# 04_io.net
KiCad netlist of a schematic drawn in Altium Designer
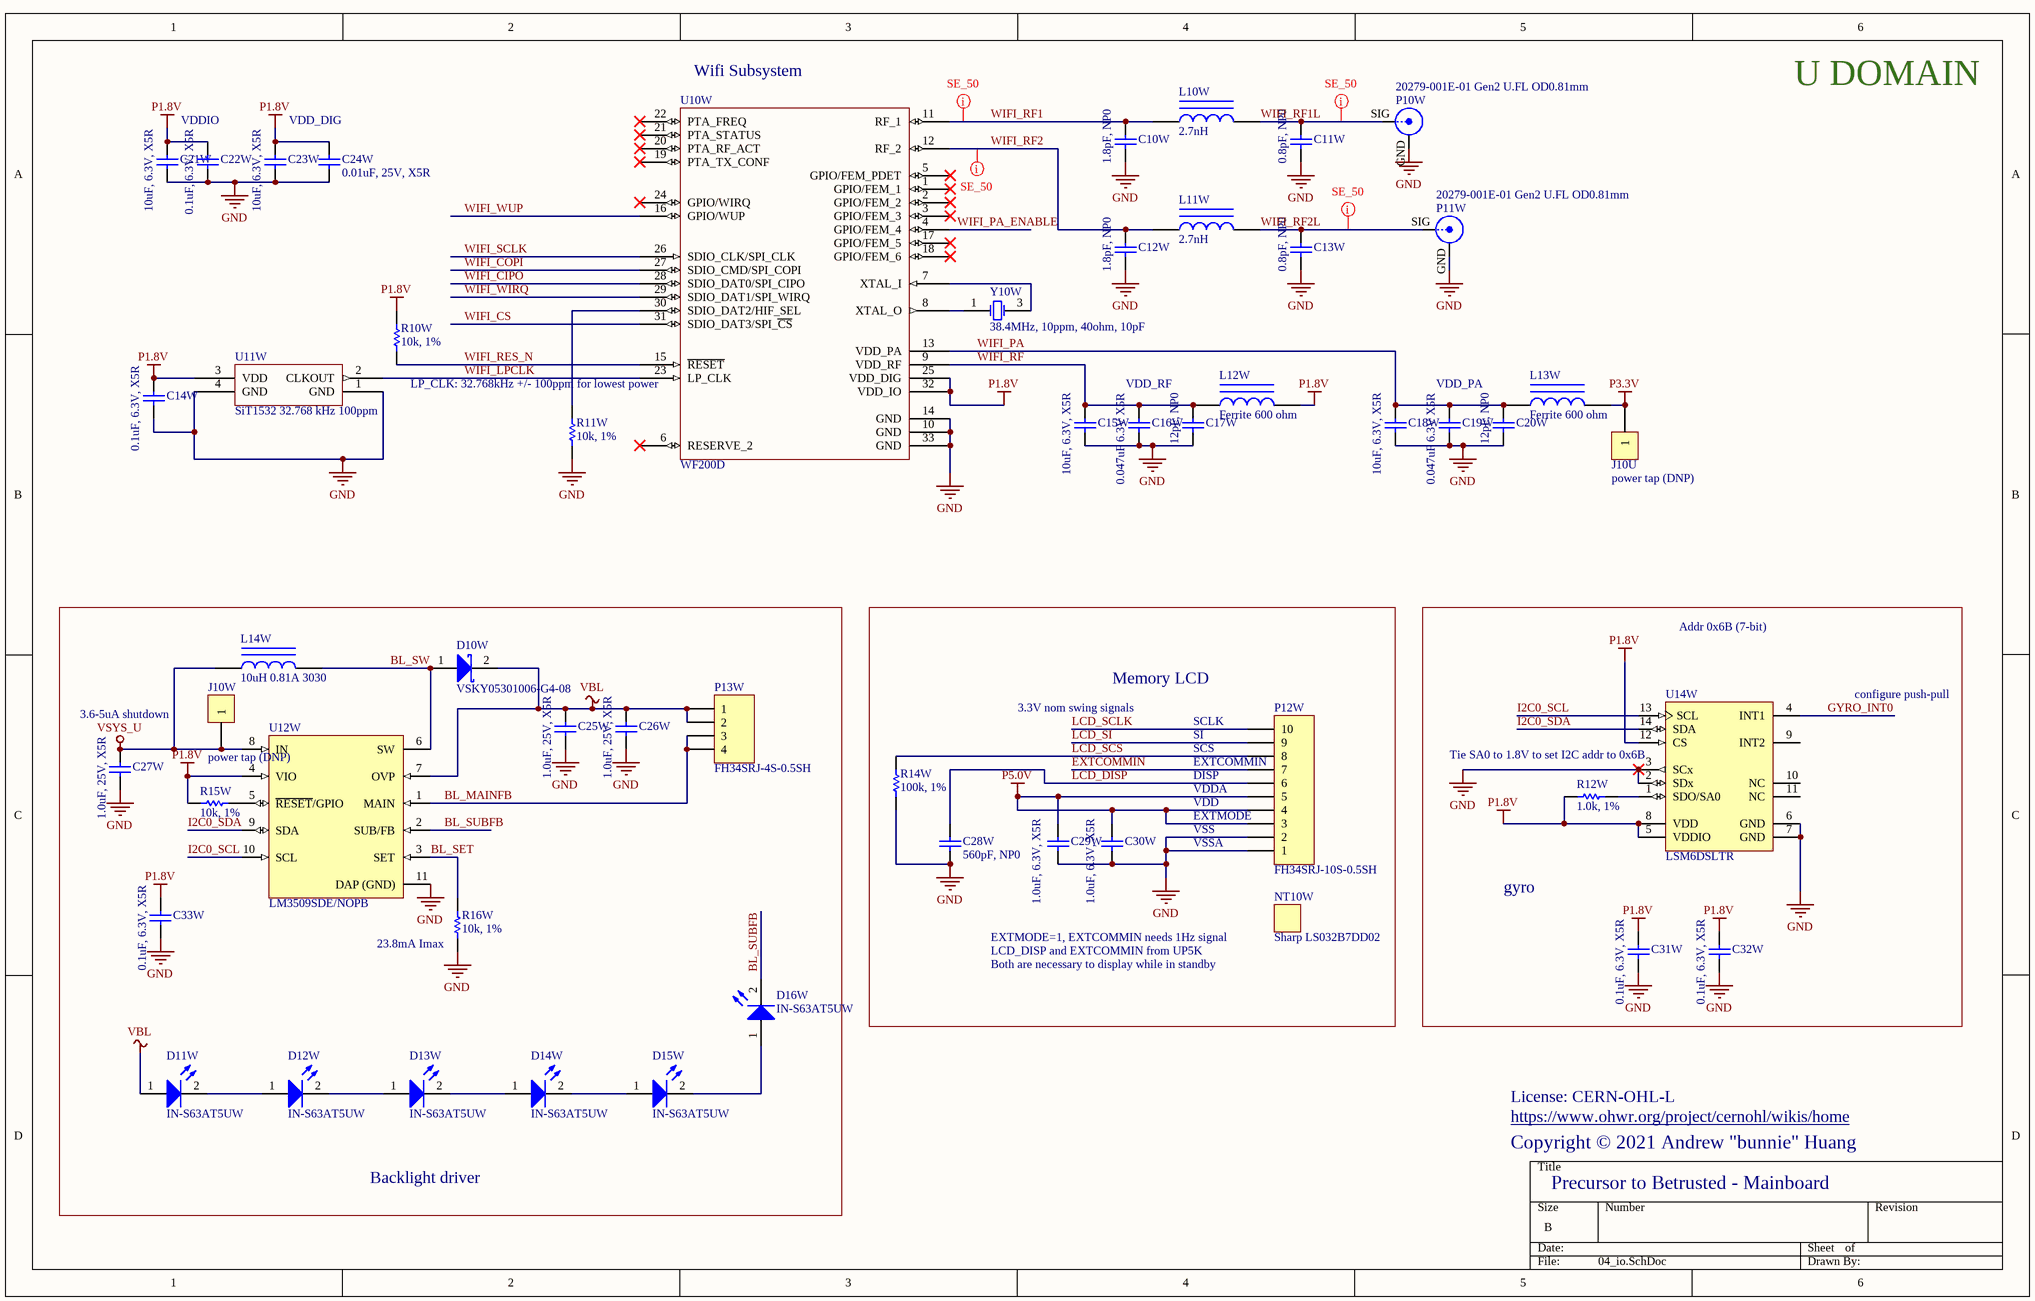
[diagram p0: 04_io.SchDoc]

(export (version "E")
  (design (tool "Eeschema 10.0.6"))
  (components
    (comp (ref "C10W")
      (value "1.8pF, NP0")
      (footprint "B_CAP0201")
      (description "Capacitor (Semiconductor SIM Model)")
      (fields (field (name "MPN") "GRM0335C1H1R8BA01D"))
      (libsource (lib "Miscellaneous Devices") (part "Cap Semi"))
    )
    (comp (ref "C11W")
      (value "0.8pF, NP0")
      (footprint "B_CAP0201")
      (description "Capacitor (Semiconductor SIM Model)")
      (fields (field (name "MPN") "GRM0335C1ER80BA01D"))
      (libsource (lib "Miscellaneous Devices") (part "Cap Semi"))
    )
    (comp (ref "C12W")
      (value "1.8pF, NP0")
      (footprint "B_CAP0201")
      (description "Capacitor (Semiconductor SIM Model)")
      (fields (field (name "MPN") "GRM0335C1H1R8BA01D"))
      (libsource (lib "Miscellaneous Devices") (part "Cap Semi"))
    )
    (comp (ref "C13W")
      (value "0.8pF, NP0")
      (footprint "B_CAP0201")
      (description "Capacitor (Semiconductor SIM Model)")
      (fields (field (name "MPN") "GRM0335C1ER80BA01D"))
      (libsource (lib "Miscellaneous Devices") (part "Cap Semi"))
    )
    (comp (ref "C14W")
      (value "0.1uF, 6.3V, X5R")
      (footprint "B_CAP0201")
      (description "Capacitor (Semiconductor SIM Model)")
      (fields (field (name "MPN") "CL03A104KQ3NNNC"))
      (libsource (lib "Miscellaneous Devices") (part "Cap Semi"))
    )
    (comp (ref "C15W")
      (value "10uF, 6.3V, X5R")
      (footprint "B_CAP0603")
      (description "Capacitor (Semiconductor SIM Model)")
      (fields (field (name "MPN") "CL10A106MQ8NNNC"))
      (libsource (lib "Miscellaneous Devices") (part "Cap Semi"))
    )
    (comp (ref "C16W")
      (value "0.047uF 6.3V X5R")
      (footprint "B_CAP0201")
      (description "Capacitor (Semiconductor SIM Model)")
      (fields (field (name "MPN") "GRM033C81A473KE05D"))
      (libsource (lib "Miscellaneous Devices") (part "Cap Semi"))
    )
    (comp (ref "C17W")
      (value "12pF, NP0")
      (footprint "B_CAP0201")
      (description "Capacitor (Semiconductor SIM Model)")
      (fields (field (name "MPN") "GRM0335C1E120JA01D"))
      (libsource (lib "Miscellaneous Devices") (part "Cap Semi"))
    )
    (comp (ref "C18W")
      (value "10uF, 6.3V, X5R")
      (footprint "B_CAP0603")
      (description "Capacitor (Semiconductor SIM Model)")
      (fields (field (name "MPN") "CL10A106MQ8NNNC"))
      (libsource (lib "Miscellaneous Devices") (part "Cap Semi"))
    )
    (comp (ref "C19W")
      (value "0.047uF 6.3V X5R")
      (footprint "B_CAP0201")
      (description "Capacitor (Semiconductor SIM Model)")
      (fields (field (name "MPN") "GRM033C81A473KE05D"))
      (libsource (lib "Miscellaneous Devices") (part "Cap Semi"))
    )
    (comp (ref "C20W")
      (value "12pF, NP0")
      (footprint "B_CAP0201")
      (description "Capacitor (Semiconductor SIM Model)")
      (fields (field (name "MPN") "GRM0335C1E120JA01D"))
      (libsource (lib "Miscellaneous Devices") (part "Cap Semi"))
    )
    (comp (ref "C21W")
      (value "10uF, 6.3V, X5R")
      (footprint "B_CAP0603")
      (description "Capacitor (Semiconductor SIM Model)")
      (fields (field (name "MPN") "CL10A106MQ8NNNC"))
      (libsource (lib "Miscellaneous Devices") (part "Cap Semi"))
    )
    (comp (ref "C22W")
      (value "0.1uF, 6.3V, X5R")
      (footprint "B_CAP0201")
      (description "Capacitor (Semiconductor SIM Model)")
      (fields (field (name "MPN") "CL03A104KQ3NNNC"))
      (libsource (lib "Miscellaneous Devices") (part "Cap Semi"))
    )
    (comp (ref "C23W")
      (value "10uF, 6.3V, X5R")
      (footprint "B_CAP0603")
      (description "Capacitor (Semiconductor SIM Model)")
      (fields (field (name "MPN") "CL10A106MQ8NNNC"))
      (libsource (lib "Miscellaneous Devices") (part "Cap Semi"))
    )
    (comp (ref "C24W")
      (value "0.01uF, 25V, X5R")
      (footprint "B_RES0201")
      (description "Capacitor (Semiconductor SIM Model)")
      (fields (field (name "MPN") "GRM033R61E103KA12D"))
      (libsource (lib "Miscellaneous Devices") (part "Cap Semi"))
    )
    (comp (ref "C25W")
      (value "1.0uF, 25V, X5R")
      (footprint "B_CAP0603")
      (description "Capacitor (Semiconductor SIM Model)")
      (fields (field (name "MPN") "CL10A105KA8NNNC"))
      (libsource (lib "Miscellaneous Devices") (part "Cap Semi"))
    )
    (comp (ref "C26W")
      (value "1.0uF, 25V, X5R")
      (footprint "B_CAP0603")
      (description "Capacitor (Semiconductor SIM Model)")
      (fields (field (name "MPN") "CL10A105KA8NNNC"))
      (libsource (lib "Miscellaneous Devices") (part "Cap Semi"))
    )
    (comp (ref "C27W")
      (value "1.0uF, 25V, X5R")
      (footprint "B_CAP0603")
      (description "Capacitor (Semiconductor SIM Model)")
      (fields (field (name "MPN") "CL10A105KA8NNNC"))
      (libsource (lib "Miscellaneous Devices") (part "Cap Semi"))
    )
    (comp (ref "C28W")
      (value "560pF, NP0")
      (footprint "B_RES0201")
      (description "Capacitor (Semiconductor SIM Model)")
      (fields (field (name "MPN") "GRM0335C1E561JA01D"))
      (libsource (lib "Miscellaneous Devices") (part "Cap Semi"))
    )
    (comp (ref "C29W")
      (value "1.0uF, 6.3V, X5R")
      (footprint "B_CAP0201")
      (description "Capacitor (Semiconductor SIM Model)")
      (fields (field (name "MPN") "GRM033R60J105MEA2D"))
      (libsource (lib "Miscellaneous Devices") (part "Cap Semi"))
    )
    (comp (ref "C30W")
      (value "1.0uF, 6.3V, X5R")
      (footprint "B_CAP0201")
      (description "Capacitor (Semiconductor SIM Model)")
      (fields (field (name "MPN") "GRM033R60J105MEA2D"))
      (libsource (lib "Miscellaneous Devices") (part "Cap Semi"))
    )
    (comp (ref "C31W")
      (value "0.1uF, 6.3V, X5R")
      (footprint "B_CAP0201")
      (description "Capacitor (Semiconductor SIM Model)")
      (fields (field (name "MPN") "CL03A104KQ3NNNC"))
      (libsource (lib "Miscellaneous Devices") (part "Cap Semi"))
    )
    (comp (ref "C32W")
      (value "0.1uF, 6.3V, X5R")
      (footprint "B_CAP0201")
      (description "Capacitor (Semiconductor SIM Model)")
      (fields (field (name "MPN") "CL03A104KQ3NNNC"))
      (libsource (lib "Miscellaneous Devices") (part "Cap Semi"))
    )
    (comp (ref "C33W")
      (value "0.1uF, 6.3V, X5R")
      (footprint "B_CAP0201")
      (description "Capacitor (Semiconductor SIM Model)")
      (fields (field (name "MPN") "CL03A104KQ3NNNC"))
      (libsource (lib "Miscellaneous Devices") (part "Cap Semi"))
    )
    (comp (ref "D10W")
      (value "VSKY05301006-G4-08")
      (footprint "B_DIO0402")
      (description "Schottky Rectifier")
      (libsource (lib "Miscellaneous Devices") (part "Diode 11DQ03"))
    )
    (comp (ref "D11W")
      (value "IN-S63AT5UW")
      (footprint "B_DIO0603")
      (description "White LED, 0603, 900mcd, 0.4mm")
      (fields (field (name "PUBLISHER") "Altium Limited"))
      (libsource (lib "Miscellaneous Devices") (part "LED2"))
    )
    (comp (ref "D12W")
      (value "IN-S63AT5UW")
      (footprint "B_DIO0603")
      (description "White LED, 0603, 900mcd, 0.4mm")
      (fields (field (name "PUBLISHER") "Altium Limited"))
      (libsource (lib "Miscellaneous Devices") (part "LED2"))
    )
    (comp (ref "D13W")
      (value "IN-S63AT5UW")
      (footprint "B_DIO0603")
      (description "White LED, 0603, 900mcd, 0.4mm")
      (fields (field (name "PUBLISHER") "Altium Limited"))
      (libsource (lib "Miscellaneous Devices") (part "LED2"))
    )
    (comp (ref "D14W")
      (value "IN-S63AT5UW")
      (footprint "B_DIO0603")
      (description "White LED, 0603, 900mcd, 0.4mm")
      (fields (field (name "PUBLISHER") "Altium Limited"))
      (libsource (lib "Miscellaneous Devices") (part "LED2"))
    )
    (comp (ref "D15W")
      (value "IN-S63AT5UW")
      (footprint "B_DIO0603")
      (description "White LED, 0603, 900mcd, 0.4mm")
      (fields (field (name "PUBLISHER") "Altium Limited"))
      (libsource (lib "Miscellaneous Devices") (part "LED2"))
    )
    (comp (ref "D16W")
      (value "IN-S63AT5UW")
      (footprint "B_DIO0603")
      (description "White LED, 0603, 900mcd, 0.4mm")
      (fields (field (name "PUBLISHER") "Altium Limited"))
      (libsource (lib "Miscellaneous Devices") (part "LED2"))
    )
    (comp (ref "J10U")
      (value "power tap (DNP)")
      (footprint "RESTAP-0603")
      (description "Connector")
      (fields (field (name "MPN") "DNP"))
      (libsource (lib "*") (part "CON1"))
    )
    (comp (ref "J10W")
      (value "power tap (DNP)")
      (footprint "RESTAP-0603")
      (description "Connector")
      (fields (field (name "MPN") "DNP"))
      (libsource (lib "") (part "CON1_1"))
    )
    (comp (ref "L10W")
      (value "2.7nH")
      (footprint "B_IND0402")
      (description "Magnetic-Core Inductor")
      (fields (field (name "MPN") "LQW15AN2N7C00"))
      (libsource (lib "Miscellaneous Devices") (part "Inductor Iron"))
    )
    (comp (ref "L11W")
      (value "2.7nH")
      (footprint "B_IND0402")
      (description "Magnetic-Core Inductor")
      (fields (field (name "MPN") "LQW15AN2N7C00"))
      (libsource (lib "Miscellaneous Devices") (part "Inductor Iron"))
    )
    (comp (ref "L12W")
      (value "Ferrite 600 ohm")
      (footprint "B_IND0603")
      (description "Magnetic-Core Inductor")
      (fields (field (name "MPN") "BLM18AG601SN1D"))
      (libsource (lib "Miscellaneous Devices") (part "Inductor Iron"))
    )
    (comp (ref "L13W")
      (value "Ferrite 600 ohm")
      (footprint "B_IND0603")
      (description "Magnetic-Core Inductor")
      (fields (field (name "MPN") "BLM18AG601SN1D"))
      (libsource (lib "Miscellaneous Devices") (part "Inductor Iron"))
    )
    (comp (ref "L14W")
      (value "10uH 0.81A 3030")
      (footprint "B_IND3030_MUR")
      (description "Magnetic-Core Inductor")
      (fields (field (name "MPN") "LQH3NPN100MJRL"))
      (libsource (lib "Miscellaneous Devices") (part "Inductor Iron"))
    )
    (comp (ref "NT10W")
      (value "Sharp LS032B7DD02")
      (description "Placeholder for non-board BOM items")
      (fields (field (name "MPN") "LS032B7DD02"))
      (libsource (lib "commonsch") (part "NOTE"))
    )
    (comp (ref "P10W")
      (value "20279-001E-01 Gen2 U.FL OD0.81mm")
      (footprint "HRS_U.FL")
      (description "U.FL Gen2 0.81mm OD, 1.62mm mated height")
      (fields (field (name "MPN") "P1163-0140R") (field (name "PUBLISHER") "Altium Limited"))
      (libsource (lib "Miscellaneous Connectors") (part "BNC"))
    )
    (comp (ref "P11W")
      (value "20279-001E-01 Gen2 U.FL OD0.81mm")
      (footprint "HRS_U.FL")
      (description "U.FL Gen2 0.81mm OD, 1.62mm mated height")
      (fields (field (name "MPN") "P1163-0140R") (field (name "PUBLISHER") "Altium Limited"))
      (libsource (lib "Miscellaneous Connectors") (part "BNC"))
    )
    (comp (ref "P12W")
      (value "FH34SRJ-10S-0.5SH")
      (footprint "HRS_FH34SRJ-10S-0.5SH(50)")
      (description "Header, 10-Pin")
      (fields (field (name "PUBLISHER") "Altium Limited"))
      (libsource (lib "Miscellaneous Connectors") (part "Header 10"))
    )
    (comp (ref "P13W")
      (value "FH34SRJ-4S-0.5SH")
      (footprint "HRS_FH34SRJ-4S-0.5SH(50)")
      (description "4-pin FPC connector")
      (fields (field (name "MPN") "FH34SRJ-4S-0.5SH(XX)") (field (name "PUBLISHER") "Altium Limited"))
      (libsource (lib "Miscellaneous Connectors") (part "Header 4"))
    )
    (comp (ref "R10W")
      (value "10k, 1%")
      (footprint "B_RES0201")
      (description "Resistor")
      (fields (field (name "MPN") "ANY"))
      (libsource (lib "Miscellaneous Devices") (part "Res1"))
    )
    (comp (ref "R11W")
      (value "10k, 1%")
      (footprint "B_RES0201")
      (description "Resistor")
      (fields (field (name "MPN") "ANY"))
      (libsource (lib "Miscellaneous Devices") (part "Res1"))
    )
    (comp (ref "R12W")
      (value "1.0k, 1%")
      (footprint "B_RES0201")
      (description "Resistor")
      (fields (field (name "MPN") "ANY"))
      (libsource (lib "Miscellaneous Devices") (part "Res1"))
    )
    (comp (ref "R14W")
      (value "100k, 1%")
      (footprint "B_RES0201")
      (description "Resistor")
      (fields (field (name "MPN") "ANY"))
      (libsource (lib "Miscellaneous Devices") (part "Res1"))
    )
    (comp (ref "R15W")
      (value "10k, 1%")
      (footprint "B_RES0201")
      (description "Resistor")
      (fields (field (name "MPN") "ANY"))
      (libsource (lib "Miscellaneous Devices") (part "Res1"))
    )
    (comp (ref "R16W")
      (value "10k, 1%")
      (footprint "B_RES0201")
      (description "Resistor")
      (fields (field (name "MPN") "ANY"))
      (libsource (lib "Miscellaneous Devices") (part "Res1"))
    )
    (comp (ref "U10W")
      (value "WF200D")
      (footprint "QFN40P400X400X90_HS-33N")
      (description "Wifi Network Coprocessor")
      (libsource (lib "commonsch-new") (part "WF200C(R)"))
    )
    (comp (ref "U11W")
      (value "SiT1532 32.768 kHz 100ppm")
      (footprint "SiTIME_CSP")
      (description "10ppm ultra low power 32.768 kHz replacement")
      (fields (field (name "MPN") "SIT1532AI-J4-DCC-32.768E"))
      (libsource (lib "altium-import") (part "root_2_SiT1532_"))
    )
    (comp (ref "U12W")
      (value "LM3509SDE/NOPB")
      (footprint "DSC0010A_V")
      (libsource (lib "commonsch-new") (part "LM3509SDE/NOPB"))
    )
    (comp (ref "U14W")
      (value "LSM6DSLTR")
      (footprint "LGA-14_2500X3000X860_N")
      (libsource (lib "commonsch-new") (part "LSM6DS3TR"))
    )
    (comp (ref "Y10W")
      (value "38.4MHz, 10ppm, 40ohm, 10pF")
      (footprint "XOSC_3.2_2.5")
      (description "Crystal Oscillator")
      (fields (field (name "MPN") "ECS-384-10-33B-CKY-TR") (field (name "PUBLISHER") "Altium Limited"))
      (libsource (lib "Miscellaneous Devices") (part "XTAL"))
    )
  )
  (nets
    (net (code "1") (name "/BL_MAINFB") (class "Default")
      (node (ref "P13W") (pin "3") (pinfunction "3_3") (pintype "passive"))
      (node (ref "P13W") (pin "4") (pinfunction "4_4") (pintype "passive"))
      (node (ref "U12W") (pin "1") (pinfunction "MAIN_1") (pintype "input"))
    )
    (net (code "2") (name "/BL_SET") (class "Default")
      (node (ref "R16W") (pin "1") (pinfunction "1_1") (pintype "passive"))
      (node (ref "U12W") (pin "3") (pinfunction "SET_3") (pintype "input"))
    )
    (net (code "3") (name "/BL_SUBFB") (class "Default")
      (node (ref "D16W") (pin "2") (pinfunction "K_2") (pintype "passive"))
      (node (ref "U12W") (pin "2") (pinfunction "SUB/FB_2") (pintype "input"))
    )
    (net (code "4") (name "/BL_SW") (class "Default")
      (node (ref "D10W") (pin "1") (pinfunction "A_1") (pintype "passive"))
      (node (ref "L14W") (pin "2") (pinfunction "2_2") (pintype "passive"))
      (node (ref "U12W") (pin "6") (pinfunction "SW_6") (pintype "power_in"))
    )
    (net (code "5") (name "/EXTCOMMIN") (class "Default")
      (node (ref "P12W") (pin "7") (pinfunction "7_7") (pintype "passive"))
    )
    (net (code "6") (name "/GYRO_INT0") (class "Default")
      (node (ref "U14W") (pin "4") (pinfunction "INT1_4") (pintype "open_collector"))
    )
    (net (code "7") (name "/I2C0_SCL") (class "Default")
      (node (ref "U12W") (pin "10") (pinfunction "SCL_10") (pintype "input"))
      (node (ref "U14W") (pin "13") (pinfunction "SCL_13") (pintype "input"))
    )
    (net (code "8") (name "/I2C0_SDA") (class "Default")
      (node (ref "U12W") (pin "9") (pinfunction "SDA_9") (pintype "bidirectional"))
      (node (ref "U14W") (pin "14") (pinfunction "SDA_14") (pintype "bidirectional"))
    )
    (net (code "9") (name "/LCD_DISP") (class "Default")
      (node (ref "C28W") (pin "1") (pinfunction "1_1") (pintype "passive"))
      (node (ref "P12W") (pin "6") (pinfunction "6_6") (pintype "passive"))
    )
    (net (code "10") (name "/LCD_SCLK") (class "Default")
      (node (ref "P12W") (pin "10") (pinfunction "10_10") (pintype "passive"))
    )
    (net (code "11") (name "/LCD_SCS") (class "Default")
      (node (ref "P12W") (pin "8") (pinfunction "8_8") (pintype "passive"))
      (node (ref "R14W") (pin "2") (pinfunction "2_2") (pintype "passive"))
    )
    (net (code "12") (name "/LCD_SI") (class "Default")
      (node (ref "P12W") (pin "9") (pinfunction "9_9") (pintype "passive"))
    )
    (net (code "13") (name "/WIFI_CIPO") (class "Default")
      (node (ref "U10W") (pin "28") (pinfunction "SDIO_DAT0/SPI_CIPO_28") (pintype "bidirectional"))
    )
    (net (code "14") (name "/WIFI_COPI") (class "Default")
      (node (ref "U10W") (pin "27") (pinfunction "SDIO_CMD/SPI_COPI_27") (pintype "bidirectional"))
    )
    (net (code "15") (name "/WIFI_CS") (class "Default")
      (node (ref "U10W") (pin "31") (pinfunction "SDIO_DAT3/SPI_~{CS}_31") (pintype "bidirectional"))
    )
    (net (code "16") (name "/WIFI_LPCLK") (class "Default")
      (node (ref "U10W") (pin "23") (pinfunction "LP_CLK_23") (pintype "input"))
      (node (ref "U11W") (pin "2") (pinfunction "CLKOUT_2") (pintype "output"))
    )
    (net (code "17") (name "/WIFI_PA") (class "Default")
      (node (ref "C18W") (pin "1") (pinfunction "1_1") (pintype "passive"))
      (node (ref "C19W") (pin "1") (pinfunction "1_1") (pintype "passive"))
      (node (ref "C20W") (pin "1") (pinfunction "1_1") (pintype "passive"))
      (node (ref "L13W") (pin "1") (pinfunction "1_1") (pintype "passive"))
      (node (ref "U10W") (pin "13") (pinfunction "VDD_PA_13") (pintype "power_in"))
    )
    (net (code "18") (name "/WIFI_PA_ENABLE") (class "Default")
      (node (ref "U10W") (pin "4") (pinfunction "GPIO/FEM_4_4") (pintype "bidirectional"))
    )
    (net (code "19") (name "/WIFI_RES_N") (class "Default")
      (node (ref "R10W") (pin "2") (pinfunction "2_2") (pintype "passive"))
      (node (ref "U10W") (pin "15") (pinfunction "~{RESET}_15") (pintype "input"))
    )
    (net (code "20") (name "/WIFI_RF") (class "Default")
      (node (ref "C15W") (pin "1") (pinfunction "1_1") (pintype "passive"))
      (node (ref "C16W") (pin "1") (pinfunction "1_1") (pintype "passive"))
      (node (ref "C17W") (pin "1") (pinfunction "1_1") (pintype "passive"))
      (node (ref "L12W") (pin "1") (pinfunction "1_1") (pintype "passive"))
      (node (ref "U10W") (pin "9") (pinfunction "VDD_RF_9") (pintype "power_in"))
    )
    (net (code "21") (name "/WIFI_RF1") (class "Default")
      (node (ref "C10W") (pin "1") (pinfunction "1_1") (pintype "passive"))
      (node (ref "L10W") (pin "1") (pinfunction "1_1") (pintype "passive"))
      (node (ref "U10W") (pin "11") (pinfunction "RF_1_11") (pintype "bidirectional"))
    )
    (net (code "22") (name "/WIFI_RF1L") (class "Default")
      (node (ref "C11W") (pin "1") (pinfunction "1_1") (pintype "passive"))
      (node (ref "L10W") (pin "2") (pinfunction "2_2") (pintype "passive"))
      (node (ref "P10W") (pin "SIG") (pinfunction "X_SIG") (pintype "passive"))
    )
    (net (code "23") (name "/WIFI_RF2") (class "Default")
      (node (ref "C12W") (pin "1") (pinfunction "1_1") (pintype "passive"))
      (node (ref "L11W") (pin "1") (pinfunction "1_1") (pintype "passive"))
      (node (ref "U10W") (pin "12") (pinfunction "RF_2_12") (pintype "bidirectional"))
    )
    (net (code "24") (name "/WIFI_RF2L") (class "Default")
      (node (ref "C13W") (pin "1") (pinfunction "1_1") (pintype "passive"))
      (node (ref "L11W") (pin "2") (pinfunction "2_2") (pintype "passive"))
      (node (ref "P11W") (pin "SIG") (pinfunction "X_SIG") (pintype "passive"))
    )
    (net (code "25") (name "/WIFI_SCLK") (class "Default")
      (node (ref "U10W") (pin "26") (pinfunction "SDIO_CLK/SPI_CLK_26") (pintype "input"))
    )
    (net (code "26") (name "/WIFI_WIRQ") (class "Default")
      (node (ref "U10W") (pin "29") (pinfunction "SDIO_DAT1/SPI_WIRQ_29") (pintype "bidirectional"))
    )
    (net (code "27") (name "/WIFI_WUP") (class "Default")
      (node (ref "U10W") (pin "16") (pinfunction "GPIO/WUP_16") (pintype "bidirectional"))
    )
    (net (code "28") (name "GND") (class "Default")
      (node (ref "C10W") (pin "2") (pinfunction "2_2") (pintype "passive"))
      (node (ref "C11W") (pin "2") (pinfunction "2_2") (pintype "passive"))
      (node (ref "C12W") (pin "2") (pinfunction "2_2") (pintype "passive"))
      (node (ref "C13W") (pin "2") (pinfunction "2_2") (pintype "passive"))
      (node (ref "C14W") (pin "2") (pinfunction "2_2") (pintype "passive"))
      (node (ref "C15W") (pin "2") (pinfunction "2_2") (pintype "passive"))
      (node (ref "C16W") (pin "2") (pinfunction "2_2") (pintype "passive"))
      (node (ref "C17W") (pin "2") (pinfunction "2_2") (pintype "passive"))
      (node (ref "C18W") (pin "2") (pinfunction "2_2") (pintype "passive"))
      (node (ref "C19W") (pin "2") (pinfunction "2_2") (pintype "passive"))
      (node (ref "C20W") (pin "2") (pinfunction "2_2") (pintype "passive"))
      (node (ref "C21W") (pin "2") (pinfunction "2_2") (pintype "passive"))
      (node (ref "C22W") (pin "2") (pinfunction "2_2") (pintype "passive"))
      (node (ref "C23W") (pin "2") (pinfunction "2_2") (pintype "passive"))
      (node (ref "C24W") (pin "2") (pinfunction "2_2") (pintype "passive"))
      (node (ref "C25W") (pin "2") (pinfunction "2_2") (pintype "passive"))
      (node (ref "C26W") (pin "2") (pinfunction "2_2") (pintype "passive"))
      (node (ref "C27W") (pin "2") (pinfunction "2_2") (pintype "passive"))
      (node (ref "C28W") (pin "2") (pinfunction "2_2") (pintype "passive"))
      (node (ref "C29W") (pin "1") (pinfunction "1_1") (pintype "passive"))
      (node (ref "C30W") (pin "1") (pinfunction "1_1") (pintype "passive"))
      (node (ref "C31W") (pin "2") (pinfunction "2_2") (pintype "passive"))
      (node (ref "C32W") (pin "2") (pinfunction "2_2") (pintype "passive"))
      (node (ref "C33W") (pin "2") (pinfunction "2_2") (pintype "passive"))
      (node (ref "P10W") (pin "GND") (pinfunction "Y_GND") (pintype "passive"))
      (node (ref "P11W") (pin "GND") (pinfunction "Y_GND") (pintype "passive"))
      (node (ref "P12W") (pin "1") (pinfunction "1_1") (pintype "passive"))
      (node (ref "P12W") (pin "2") (pinfunction "2_2") (pintype "passive"))
      (node (ref "R11W") (pin "2") (pinfunction "2_2") (pintype "passive"))
      (node (ref "R14W") (pin "1") (pinfunction "1_1") (pintype "passive"))
      (node (ref "R16W") (pin "2") (pinfunction "2_2") (pintype "passive"))
      (node (ref "U10W") (pin "10") (pinfunction "GND_10") (pintype "power_in"))
      (node (ref "U10W") (pin "14") (pinfunction "GND_14") (pintype "power_in"))
      (node (ref "U10W") (pin "33") (pinfunction "GND_33") (pintype "power_in"))
      (node (ref "U11W") (pin "1") (pinfunction "GND_1") (pintype "power_in"))
      (node (ref "U11W") (pin "4") (pinfunction "GND_4") (pintype "power_in"))
      (node (ref "U12W") (pin "11") (pinfunction "DAP_(GND)_11") (pintype "power_in"))
      (node (ref "U14W") (pin "2") (pinfunction "SDx_2") (pintype "bidirectional"))
      (node (ref "U14W") (pin "3") (pinfunction "SCx_3") (pintype "output"))
      (node (ref "U14W") (pin "6") (pinfunction "GND_6") (pintype "power_in"))
      (node (ref "U14W") (pin "7") (pinfunction "GND_7") (pintype "power_in"))
    )
    (net (code "29") (name "Net-(D11W-K)") (class "Default")
      (node (ref "D11W") (pin "2") (pinfunction "K_2") (pintype "passive"))
      (node (ref "D12W") (pin "1") (pinfunction "A_1") (pintype "passive"))
    )
    (net (code "30") (name "Net-(D12W-K)") (class "Default")
      (node (ref "D12W") (pin "2") (pinfunction "K_2") (pintype "passive"))
      (node (ref "D13W") (pin "1") (pinfunction "A_1") (pintype "passive"))
    )
    (net (code "31") (name "Net-(D13W-K)") (class "Default")
      (node (ref "D13W") (pin "2") (pinfunction "K_2") (pintype "passive"))
      (node (ref "D14W") (pin "1") (pinfunction "A_1") (pintype "passive"))
    )
    (net (code "32") (name "Net-(D14W-K)") (class "Default")
      (node (ref "D14W") (pin "2") (pinfunction "K_2") (pintype "passive"))
      (node (ref "D15W") (pin "1") (pinfunction "A_1") (pintype "passive"))
    )
    (net (code "33") (name "Net-(D15W-K)") (class "Default")
      (node (ref "D15W") (pin "2") (pinfunction "K_2") (pintype "passive"))
      (node (ref "D16W") (pin "1") (pinfunction "A_1") (pintype "passive"))
    )
    (net (code "34") (name "Net-(U10W-SDIO_DAT2{slash}HIF_SEL)") (class "Default")
      (node (ref "R11W") (pin "1") (pinfunction "1_1") (pintype "passive"))
      (node (ref "U10W") (pin "30") (pinfunction "SDIO_DAT2/HIF_SEL_30") (pintype "bidirectional"))
    )
    (net (code "35") (name "Net-(U10W-XTAL_I)") (class "Default")
      (node (ref "U10W") (pin "7") (pinfunction "XTAL_I_7") (pintype "input"))
      (node (ref "Y10W") (pin "3") (pinfunction "OSC2_3") (pintype "passive"))
    )
    (net (code "36") (name "Net-(U10W-XTAL_O)") (class "Default")
      (node (ref "U10W") (pin "8") (pinfunction "XTAL_O_8") (pintype "output"))
      (node (ref "Y10W") (pin "1") (pinfunction "OSC1_1") (pintype "passive"))
    )
    (net (code "37") (name "Net-(U12W-~{RESET}{slash}GPIO)") (class "Default")
      (node (ref "R15W") (pin "2") (pinfunction "2_2") (pintype "passive"))
      (node (ref "U12W") (pin "5") (pinfunction "~{RESET}/GPIO_5") (pintype "bidirectional"))
    )
    (net (code "38") (name "Net-(U14W-SDO{slash}SA0)") (class "Default")
      (node (ref "R12W") (pin "1") (pinfunction "1_1") (pintype "passive"))
      (node (ref "U14W") (pin "1") (pinfunction "SDO/SA0_1") (pintype "bidirectional"))
    )
    (net (code "39") (name "P1.8V") (class "Default")
      (node (ref "C14W") (pin "1") (pinfunction "1_1") (pintype "passive"))
      (node (ref "C21W") (pin "1") (pinfunction "1_1") (pintype "passive"))
      (node (ref "C22W") (pin "1") (pinfunction "1_1") (pintype "passive"))
      (node (ref "C23W") (pin "1") (pinfunction "1_1") (pintype "passive"))
      (node (ref "C24W") (pin "1") (pinfunction "1_1") (pintype "passive"))
      (node (ref "C31W") (pin "1") (pinfunction "1_1") (pintype "passive"))
      (node (ref "C32W") (pin "1") (pinfunction "1_1") (pintype "passive"))
      (node (ref "C33W") (pin "1") (pinfunction "1_1") (pintype "passive"))
      (node (ref "L12W") (pin "2") (pinfunction "2_2") (pintype "passive"))
      (node (ref "R10W") (pin "1") (pinfunction "1_1") (pintype "passive"))
      (node (ref "R12W") (pin "2") (pinfunction "2_2") (pintype "passive"))
      (node (ref "R15W") (pin "1") (pinfunction "1_1") (pintype "passive"))
      (node (ref "U10W") (pin "25") (pinfunction "VDD_DIG_25") (pintype "power_in"))
      (node (ref "U10W") (pin "32") (pinfunction "VDD_IO_32") (pintype "power_in"))
      (node (ref "U11W") (pin "3") (pinfunction "VDD_3") (pintype "power_in"))
      (node (ref "U12W") (pin "4") (pinfunction "VIO_4") (pintype "input"))
      (node (ref "U14W") (pin "12") (pinfunction "CS_12") (pintype "input"))
      (node (ref "U14W") (pin "5") (pinfunction "VDDIO_5") (pintype "power_in"))
      (node (ref "U14W") (pin "8") (pinfunction "VDD_8") (pintype "power_in"))
    )
    (net (code "40") (name "P3.3V") (class "Default")
      (node (ref "J10U") (pin "1") (pinfunction "1_1") (pintype "passive"))
      (node (ref "L13W") (pin "2") (pinfunction "2_2") (pintype "passive"))
    )
    (net (code "41") (name "P5.0V") (class "Default")
      (node (ref "C29W") (pin "2") (pinfunction "2_2") (pintype "passive"))
      (node (ref "C30W") (pin "2") (pinfunction "2_2") (pintype "passive"))
      (node (ref "P12W") (pin "3") (pinfunction "3_3") (pintype "passive"))
      (node (ref "P12W") (pin "4") (pinfunction "4_4") (pintype "passive"))
      (node (ref "P12W") (pin "5") (pinfunction "5_5") (pintype "passive"))
    )
    (net (code "42") (name "VBL") (class "Default")
      (node (ref "C25W") (pin "1") (pinfunction "1_1") (pintype "passive"))
      (node (ref "C26W") (pin "1") (pinfunction "1_1") (pintype "passive"))
      (node (ref "D10W") (pin "2") (pinfunction "K_2") (pintype "passive"))
      (node (ref "D11W") (pin "1") (pinfunction "A_1") (pintype "passive"))
      (node (ref "P13W") (pin "1") (pinfunction "1_1") (pintype "passive"))
      (node (ref "P13W") (pin "2") (pinfunction "2_2") (pintype "passive"))
      (node (ref "U12W") (pin "7") (pinfunction "OVP_7") (pintype "input"))
    )
    (net (code "43") (name "VSYS_U") (class "Default")
      (node (ref "C27W") (pin "1") (pinfunction "1_1") (pintype "passive"))
      (node (ref "J10W") (pin "1") (pinfunction "1_1") (pintype "passive"))
      (node (ref "L14W") (pin "1") (pinfunction "1_1") (pintype "passive"))
      (node (ref "U12W") (pin "8") (pinfunction "IN_8") (pintype "input"))
    )
    (net (code "44") (name "unconnected-(U10W-GPIO{slash}FEM_1-Pad1)") (class "Default")
      (node (ref "U10W") (pin "1") (pinfunction "GPIO/FEM_1_1") (pintype "bidirectional+no_connect"))
    )
    (net (code "45") (name "unconnected-(U10W-GPIO{slash}FEM_2-Pad2)") (class "Default")
      (node (ref "U10W") (pin "2") (pinfunction "GPIO/FEM_2_2") (pintype "bidirectional+no_connect"))
    )
    (net (code "46") (name "unconnected-(U10W-GPIO{slash}FEM_3-Pad3)") (class "Default")
      (node (ref "U10W") (pin "3") (pinfunction "GPIO/FEM_3_3") (pintype "bidirectional+no_connect"))
    )
    (net (code "47") (name "unconnected-(U10W-GPIO{slash}FEM_5-Pad17)") (class "Default")
      (node (ref "U10W") (pin "17") (pinfunction "GPIO/FEM_5_17") (pintype "bidirectional+no_connect"))
    )
    (net (code "48") (name "unconnected-(U10W-GPIO{slash}FEM_6-Pad18)") (class "Default")
      (node (ref "U10W") (pin "18") (pinfunction "GPIO/FEM_6_18") (pintype "bidirectional+no_connect"))
    )
    (net (code "49") (name "unconnected-(U10W-GPIO{slash}FEM_PDET-Pad5)") (class "Default")
      (node (ref "U10W") (pin "5") (pinfunction "GPIO/FEM_PDET_5") (pintype "bidirectional+no_connect"))
    )
    (net (code "50") (name "unconnected-(U10W-GPIO{slash}WIRQ-Pad24)") (class "Default")
      (node (ref "U10W") (pin "24") (pinfunction "GPIO/WIRQ_24") (pintype "bidirectional+no_connect"))
    )
    (net (code "51") (name "unconnected-(U10W-PTA_FREQ-Pad22)") (class "Default")
      (node (ref "U10W") (pin "22") (pinfunction "PTA_FREQ_22") (pintype "bidirectional+no_connect"))
    )
    (net (code "52") (name "unconnected-(U10W-PTA_RF_ACT-Pad20)") (class "Default")
      (node (ref "U10W") (pin "20") (pinfunction "PTA_RF_ACT_20") (pintype "bidirectional+no_connect"))
    )
    (net (code "53") (name "unconnected-(U10W-PTA_STATUS-Pad21)") (class "Default")
      (node (ref "U10W") (pin "21") (pinfunction "PTA_STATUS_21") (pintype "bidirectional+no_connect"))
    )
    (net (code "54") (name "unconnected-(U10W-PTA_TX_CONF-Pad19)") (class "Default")
      (node (ref "U10W") (pin "19") (pinfunction "PTA_TX_CONF_19") (pintype "bidirectional+no_connect"))
    )
    (net (code "55") (name "unconnected-(U10W-RESERVE_2-Pad6)") (class "Default")
      (node (ref "U10W") (pin "6") (pinfunction "RESERVE_2_6") (pintype "bidirectional+no_connect"))
    )
    (net (code "56") (name "unconnected-(U14W-INT2-Pad9)") (class "Default")
      (node (ref "U14W") (pin "9") (pinfunction "INT2_9") (pintype "open_collector"))
    )
    (net (code "57") (name "unconnected-(U14W-NC-Pad10)") (class "Default")
      (node (ref "U14W") (pin "10") (pinfunction "NC_10") (pintype "passive"))
    )
    (net (code "58") (name "unconnected-(U14W-NC-Pad11)") (class "Default")
      (node (ref "U14W") (pin "11") (pinfunction "NC_11") (pintype "passive"))
    )
  )
)
